# w20-cloudV1-_3_3_OHW.net
KiCad netlist of a schematic drawn in EAGLE
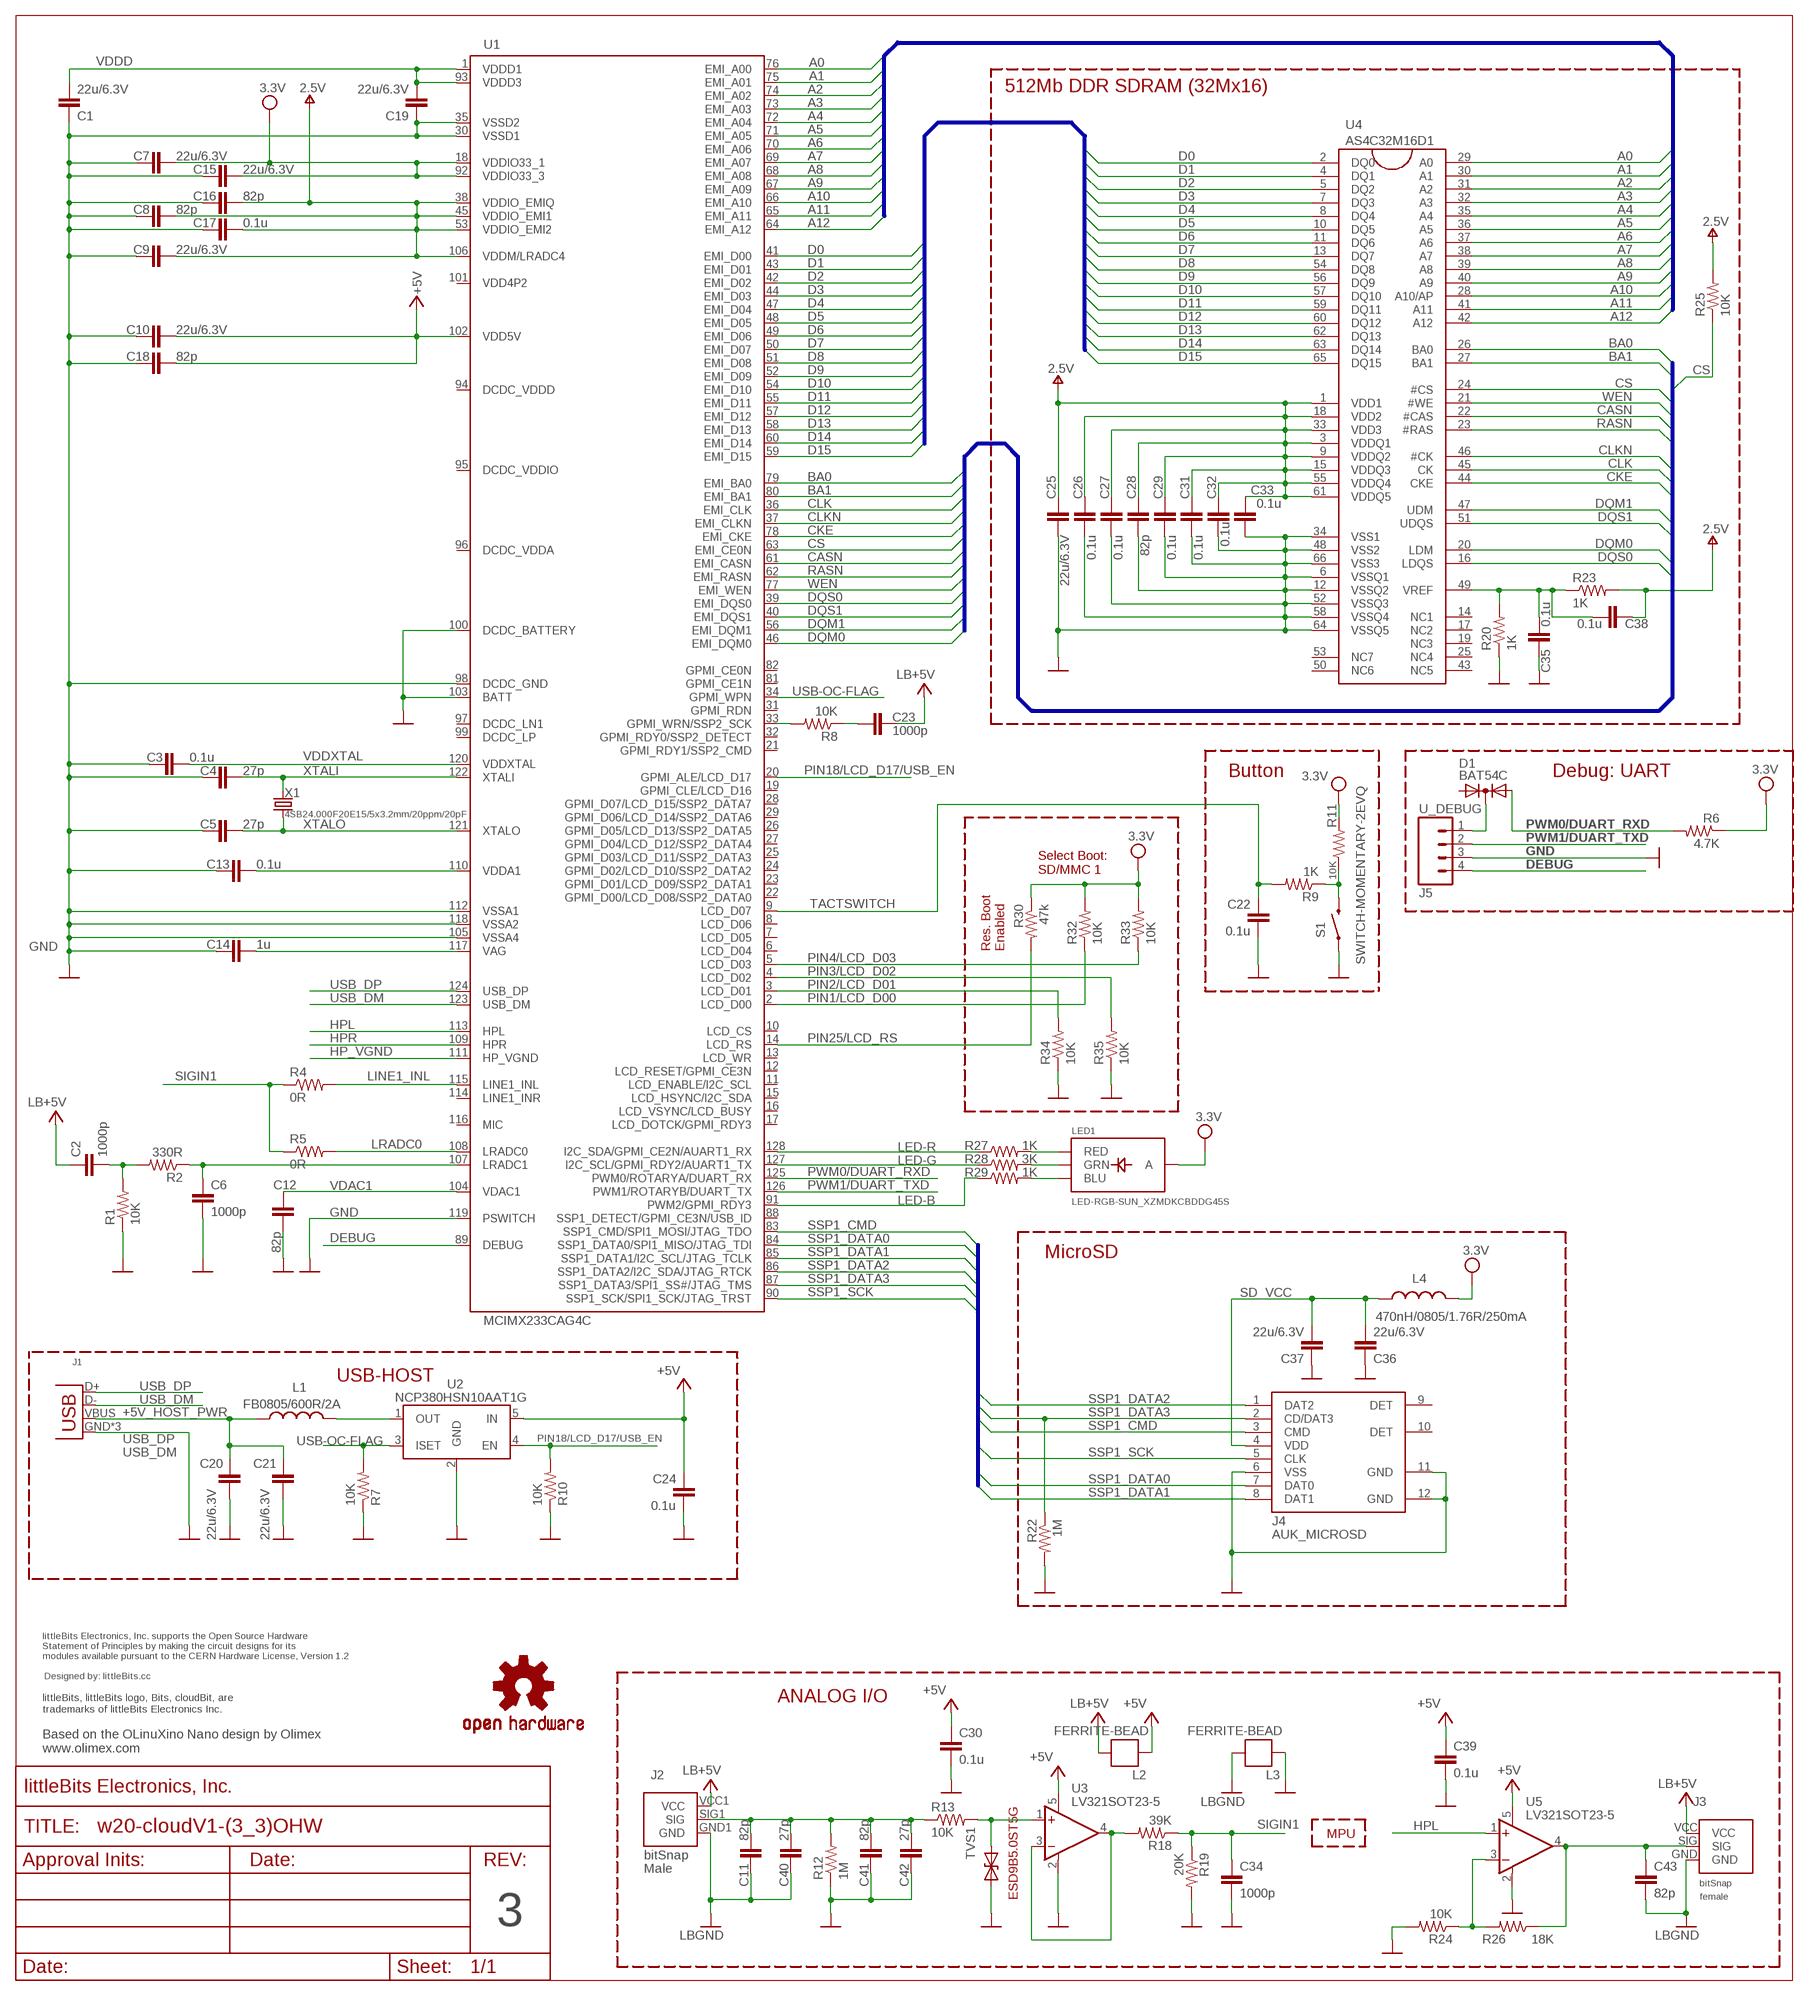
[diagram p0: schematic, sheet 1]

(export (version "E")
  (design (tool "Eeschema 10.0.6"))
  (components
    (comp (ref "C1")
      (value "22u/6.3V")
      (footprint "eagle-import:CAP-0603")
      (libsource (lib "eagle-import") (part "CAPCAP-0603"))
    )
    (comp (ref "C2")
      (value "1000p")
      (footprint "eagle-import:CAP-0603")
      (libsource (lib "eagle-import") (part "CAPCAP-0603"))
    )
    (comp (ref "C3")
      (value "0.1u")
      (footprint "eagle-import:CAP-0402")
      (libsource (lib "eagle-import") (part "CAPCAP-0402"))
    )
    (comp (ref "C4")
      (value "27p")
      (footprint "eagle-import:CAP-0402")
      (libsource (lib "eagle-import") (part "CAPCAP-0402"))
    )
    (comp (ref "C5")
      (value "27p")
      (footprint "eagle-import:CAP-0402")
      (libsource (lib "eagle-import") (part "CAPCAP-0402"))
    )
    (comp (ref "C6")
      (value "1000p")
      (footprint "eagle-import:CAP-0402")
      (libsource (lib "eagle-import") (part "CAPCAP-0402"))
    )
    (comp (ref "C7")
      (value "22u/6.3V")
      (footprint "eagle-import:CAP-0603")
      (libsource (lib "eagle-import") (part "CAPCAP-0603"))
    )
    (comp (ref "C8")
      (value "82p")
      (footprint "eagle-import:CAP-0402")
      (libsource (lib "eagle-import") (part "CAPCAP-0402"))
    )
    (comp (ref "C9")
      (value "22u/6.3V")
      (footprint "eagle-import:CAP-0603")
      (libsource (lib "eagle-import") (part "CAPCAP-0603"))
    )
    (comp (ref "C10")
      (value "22u/6.3V")
      (footprint "eagle-import:CAP-0603")
      (libsource (lib "eagle-import") (part "CAPCAP-0603"))
    )
    (comp (ref "C11")
      (value "82p")
      (footprint "eagle-import:CAP-0402")
      (libsource (lib "eagle-import") (part "CAPCAP-0402"))
    )
    (comp (ref "C12")
      (value "82p")
      (footprint "eagle-import:CAP-0402")
      (libsource (lib "eagle-import") (part "CAPCAP-0402"))
    )
    (comp (ref "C13")
      (value "0.1u")
      (footprint "eagle-import:CAP-0402")
      (libsource (lib "eagle-import") (part "CAPCAP-0402"))
    )
    (comp (ref "C14")
      (value "1u")
      (footprint "eagle-import:CAP-0402")
      (libsource (lib "eagle-import") (part "CAPCAP-0402"))
    )
    (comp (ref "C15")
      (value "22u/6.3V")
      (footprint "eagle-import:CAP-0603")
      (libsource (lib "eagle-import") (part "CAPCAP-0603"))
    )
    (comp (ref "C16")
      (value "82p")
      (footprint "eagle-import:CAP-0402")
      (libsource (lib "eagle-import") (part "CAPCAP-0402"))
    )
    (comp (ref "C17")
      (value "0.1u")
      (footprint "eagle-import:CAP-0402")
      (libsource (lib "eagle-import") (part "CAPCAP-0402"))
    )
    (comp (ref "C18")
      (value "82p")
      (footprint "eagle-import:CAP-0402")
      (libsource (lib "eagle-import") (part "CAPCAP-0402"))
    )
    (comp (ref "C19")
      (value "22u/6.3V")
      (footprint "eagle-import:CAP-0603")
      (libsource (lib "eagle-import") (part "CAPCAP-0603"))
    )
    (comp (ref "C20")
      (value "22u/6.3V")
      (footprint "eagle-import:CAP-0603")
      (libsource (lib "eagle-import") (part "CAPCAP-0603"))
    )
    (comp (ref "C21")
      (value "22u/6.3V")
      (footprint "eagle-import:CAP-0603")
      (libsource (lib "eagle-import") (part "CAPCAP-0603"))
    )
    (comp (ref "C22")
      (value "0.1u")
      (footprint "eagle-import:CAP-0402")
      (libsource (lib "eagle-import") (part "CAPCAP-0402"))
    )
    (comp (ref "C23")
      (value "1000p")
      (footprint "eagle-import:CAP-0603")
      (libsource (lib "eagle-import") (part "CAPCAP-0603"))
    )
    (comp (ref "C24")
      (value "0.1u")
      (footprint "eagle-import:CAP-0402")
      (libsource (lib "eagle-import") (part "CAPCAP-0402"))
    )
    (comp (ref "C25")
      (value "22u/6.3V")
      (footprint "eagle-import:CAP-0603")
      (libsource (lib "eagle-import") (part "CAPCAP-0603"))
    )
    (comp (ref "C26")
      (value "0.1u")
      (footprint "eagle-import:CAP-0402")
      (libsource (lib "eagle-import") (part "CAPCAP-0402"))
    )
    (comp (ref "C27")
      (value "0.1u")
      (footprint "eagle-import:CAP-0402")
      (libsource (lib "eagle-import") (part "CAPCAP-0402"))
    )
    (comp (ref "C28")
      (value "82p")
      (footprint "eagle-import:CAP-0402")
      (libsource (lib "eagle-import") (part "CAPCAP-0402"))
    )
    (comp (ref "C29")
      (value "0.1u")
      (footprint "eagle-import:CAP-0402")
      (libsource (lib "eagle-import") (part "CAPCAP-0402"))
    )
    (comp (ref "C30")
      (value "0.1u")
      (footprint "eagle-import:CAP-0402")
      (libsource (lib "eagle-import") (part "CAPCAP-0402"))
    )
    (comp (ref "C31")
      (value "0.1u")
      (footprint "eagle-import:CAP-0402")
      (libsource (lib "eagle-import") (part "CAPCAP-0402"))
    )
    (comp (ref "C32")
      (value "0.1u")
      (footprint "eagle-import:CAP-0402")
      (libsource (lib "eagle-import") (part "CAPCAP-0402"))
    )
    (comp (ref "C33")
      (value "0.1u")
      (footprint "eagle-import:CAP-0402")
      (libsource (lib "eagle-import") (part "CAPCAP-0402"))
    )
    (comp (ref "C34")
      (value "1000p")
      (footprint "eagle-import:CAP-0402")
      (libsource (lib "eagle-import") (part "CAPCAP-0402"))
    )
    (comp (ref "C35")
      (value "0.1u")
      (footprint "eagle-import:CAP-0402")
      (libsource (lib "eagle-import") (part "CAPCAP-0402"))
    )
    (comp (ref "C36")
      (value "22u/6.3V")
      (footprint "eagle-import:CAP-0603")
      (libsource (lib "eagle-import") (part "CAPCAP-0603"))
    )
    (comp (ref "C37")
      (value "22u/6.3V")
      (footprint "eagle-import:CAP-0603")
      (libsource (lib "eagle-import") (part "CAPCAP-0603"))
    )
    (comp (ref "C38")
      (value "0.1u")
      (footprint "eagle-import:CAP-0402")
      (libsource (lib "eagle-import") (part "CAPCAP-0402"))
    )
    (comp (ref "C39")
      (value "0.1u")
      (footprint "eagle-import:CAP-0402")
      (libsource (lib "eagle-import") (part "CAPCAP-0402"))
    )
    (comp (ref "C40")
      (value "27p")
      (footprint "eagle-import:CAP-0402")
      (libsource (lib "eagle-import") (part "CAPCAP-0402"))
    )
    (comp (ref "C41")
      (value "82p")
      (footprint "eagle-import:CAP-0402")
      (libsource (lib "eagle-import") (part "CAPCAP-0402"))
    )
    (comp (ref "C42")
      (value "27p")
      (footprint "eagle-import:CAP-0402")
      (libsource (lib "eagle-import") (part "CAPCAP-0402"))
    )
    (comp (ref "C43")
      (value "82p")
      (footprint "eagle-import:CAP-0402")
      (libsource (lib "eagle-import") (part "CAPCAP-0402"))
    )
    (comp (ref "D1")
      (value "BAT54C")
      (footprint "eagle-import:SOT23C")
      (libsource (lib "eagle-import") (part "DIODE_AC-CA_"))
    )
    (comp (ref "J1")
      (value "USBFEMALE")
      (footprint "eagle-import:USB-A-H-FEMALE")
      (libsource (lib "eagle-import") (part "USBFEMALE"))
    )
    (comp (ref "J2")
      (value "BITSNAP_V03_MALE")
      (footprint "eagle-import:BITSNAP_V03_MALE")
      (libsource (lib "eagle-import") (part "BITSNAP_V03_MALE"))
    )
    (comp (ref "J3")
      (value "BITSNAP_V03_FEMALE")
      (footprint "eagle-import:BITSNAP_V03_FEMALE")
      (libsource (lib "eagle-import") (part "BITSNAP_V03_FEMALE"))
    )
    (comp (ref "J4")
      (value "AUK_MICROSD")
      (footprint "eagle-import:AUK_TFC08WP01-R1K-H")
      (libsource (lib "eagle-import") (part "AUK_MICROSD"))
    )
    (comp (ref "J5")
      (value "U_DEBUG")
      (footprint "eagle-import:SIP4-SM-0.1IN-NOS.S.")
      (libsource (lib "eagle-import") (part "HDR-4SM_SML"))
    )
    (comp (ref "L1")
      (value "FB0805/600R/2A")
      (footprint "eagle-import:L0805_5MIL_DWS")
      (libsource (lib "eagle-import") (part "L-USL0805_5MIL_DWS"))
    )
    (comp (ref "L2")
      (value "FERRITE-BEAD")
      (footprint "eagle-import:R0603")
      (libsource (lib "eagle-import") (part "FERRITE-BEAD"))
    )
    (comp (ref "L3")
      (value "FERRITE-BEAD")
      (footprint "eagle-import:R0603")
      (libsource (lib "eagle-import") (part "FERRITE-BEAD"))
    )
    (comp (ref "L4")
      (value "470nH/0805/1.76R/250mA")
      (footprint "eagle-import:L0805_5MIL_DWS")
      (libsource (lib "eagle-import") (part "L-USL0805_5MIL_DWS"))
    )
    (comp (ref "LED1")
      (value "LED-RGB-SUN_XZMDKCBDDG45S")
      (footprint "eagle-import:LED-RGB-SUN_XZMDKCBDDG45S")
      (libsource (lib "eagle-import") (part "LED-RGB-SUN_XZMDKCBDDG45S"))
    )
    (comp (ref "R1")
      (value "10K")
      (footprint "eagle-import:RES-0603")
      (libsource (lib "eagle-import") (part "RESISTOR0603"))
    )
    (comp (ref "R2")
      (value "330R")
      (footprint "eagle-import:RES-0603")
      (libsource (lib "eagle-import") (part "RESISTOR0603"))
    )
    (comp (ref "R4")
      (value "0R")
      (footprint "eagle-import:RES-0603")
      (libsource (lib "eagle-import") (part "RESISTOR0603"))
    )
    (comp (ref "R5")
      (value "0R")
      (footprint "eagle-import:RES-0603")
      (libsource (lib "eagle-import") (part "RESISTOR0603"))
    )
    (comp (ref "R6")
      (value "4.7K")
      (footprint "eagle-import:RES-0603")
      (libsource (lib "eagle-import") (part "RESISTOR0603"))
    )
    (comp (ref "R7")
      (value "10K")
      (footprint "eagle-import:RES-0603")
      (libsource (lib "eagle-import") (part "RESISTOR0603"))
    )
    (comp (ref "R8")
      (value "10K")
      (footprint "eagle-import:RES-0603")
      (libsource (lib "eagle-import") (part "RESISTOR0603"))
    )
    (comp (ref "R9")
      (value "1K")
      (footprint "eagle-import:RES-0603")
      (libsource (lib "eagle-import") (part "RESISTOR0603"))
    )
    (comp (ref "R10")
      (value "10K")
      (footprint "eagle-import:RES-0603")
      (libsource (lib "eagle-import") (part "RESISTOR0603"))
    )
    (comp (ref "R11")
      (value "10K")
      (footprint "eagle-import:RES-0603")
      (libsource (lib "eagle-import") (part "RESISTOR0603"))
    )
    (comp (ref "R12")
      (value "1M")
      (footprint "eagle-import:RES-0603")
      (libsource (lib "eagle-import") (part "RESISTOR0603"))
    )
    (comp (ref "R13")
      (value "10K")
      (footprint "eagle-import:RES-0603")
      (libsource (lib "eagle-import") (part "RESISTOR0603"))
    )
    (comp (ref "R18")
      (value "39K")
      (footprint "eagle-import:RES-0603")
      (libsource (lib "eagle-import") (part "RESISTOR0603"))
    )
    (comp (ref "R19")
      (value "20K")
      (footprint "eagle-import:RES-0603")
      (libsource (lib "eagle-import") (part "RESISTOR0603"))
    )
    (comp (ref "R20")
      (value "1K")
      (footprint "eagle-import:RES-0603")
      (libsource (lib "eagle-import") (part "RESISTOR0603"))
    )
    (comp (ref "R22")
      (value "1M")
      (footprint "eagle-import:RES-0603")
      (libsource (lib "eagle-import") (part "RESISTOR0603"))
    )
    (comp (ref "R23")
      (value "1K")
      (footprint "eagle-import:RES-0603")
      (libsource (lib "eagle-import") (part "RESISTOR0603"))
    )
    (comp (ref "R24")
      (value "10K")
      (footprint "eagle-import:RES-0603")
      (libsource (lib "eagle-import") (part "RESISTOR0603"))
    )
    (comp (ref "R25")
      (value "10K")
      (footprint "eagle-import:RES-0603")
      (libsource (lib "eagle-import") (part "RESISTOR0603"))
    )
    (comp (ref "R26")
      (value "18K")
      (footprint "eagle-import:RES-0603")
      (libsource (lib "eagle-import") (part "RESISTOR0603"))
    )
    (comp (ref "R27")
      (value "1K")
      (footprint "eagle-import:RES-0603")
      (libsource (lib "eagle-import") (part "RESISTOR0603"))
    )
    (comp (ref "R28")
      (value "3K")
      (footprint "eagle-import:RES-0603")
      (libsource (lib "eagle-import") (part "RESISTOR0603"))
    )
    (comp (ref "R29")
      (value "1K")
      (footprint "eagle-import:RES-0603")
      (libsource (lib "eagle-import") (part "RESISTOR0603"))
    )
    (comp (ref "R30")
      (value "47k")
      (footprint "eagle-import:RES-0603")
      (libsource (lib "eagle-import") (part "RESISTOR0603"))
    )
    (comp (ref "R32")
      (value "10K")
      (footprint "eagle-import:RES-0603")
      (libsource (lib "eagle-import") (part "RESISTOR0603"))
    )
    (comp (ref "R33")
      (value "10K")
      (footprint "eagle-import:RES-0603")
      (libsource (lib "eagle-import") (part "RESISTOR0603"))
    )
    (comp (ref "R34")
      (value "10K")
      (footprint "eagle-import:RES-0603")
      (libsource (lib "eagle-import") (part "RESISTOR0603"))
    )
    (comp (ref "R35")
      (value "10K")
      (footprint "eagle-import:RES-0603")
      (libsource (lib "eagle-import") (part "RESISTOR0603"))
    )
    (comp (ref "S1")
      (value "SWITCH-MOMENTARY-2EVQ")
      (footprint "eagle-import:TACTILE-SWITCH-EVQ-PE104K")
      (libsource (lib "eagle-import") (part "SWITCH-MOMENTARY-2EVQ"))
    )
    (comp (ref "TVS1")
      (value "DIODE-TVSSOD-923")
      (footprint "eagle-import:SOD-923")
      (fields (field (name "MPN") "ESD9B5.0ST5G"))
      (libsource (lib "eagle-import") (part "DIODE-TVSSOD-923"))
    )
    (comp (ref "U$2")
      (value "OSHWCREDIT")
      (footprint "eagle-import:OSHWCREDIT")
      (libsource (lib "eagle-import") (part "OSHWCREDIT"))
    )
    (comp (ref "U$4")
      (value "OSHW-LOGOL")
      (footprint "eagle-import:OSHW-LOGO-L")
      (libsource (lib "eagle-import") (part "OSHW-LOGOL"))
    )
    (comp (ref "U$5")
      (value "FRAME-LETTER-OHWOHW")
      (footprint "eagle-import:FABDWG01-OHW")
      (libsource (lib "eagle-import") (part "FRAME-LETTER-OHWOHW"))
    )
    (comp (ref "U1")
      (value "MCIMX233CAG4C")
      (footprint "eagle-import:TQFP128LD")
      (libsource (lib "eagle-import") (part "MCIMX233DAG4B_LD"))
    )
    (comp (ref "U2")
      (value "NCP380HSN10AAT1G")
      (footprint "eagle-import:SOT23-5")
      (libsource (lib "eagle-import") (part "SY6280"))
    )
    (comp (ref "U3")
      (value "LV321SOT23-5")
      (footprint "eagle-import:SOT23-5")
      (libsource (lib "eagle-import") (part "LV321SOT23-5"))
    )
    (comp (ref "U4")
      (value "AS4C32M16D1")
      (footprint "eagle-import:66TSOP-II")
      (libsource (lib "eagle-import") (part "HY5DU121622D(L)T(P)-J"))
    )
    (comp (ref "U5")
      (value "LV321SOT23-5")
      (footprint "eagle-import:SOT23-5")
      (libsource (lib "eagle-import") (part "LV321SOT23-5"))
    )
    (comp (ref "X1")
      (value "4SB24.000F20E15/5x3.2mm/20ppm/20pF")
      (footprint "eagle-import:HCX-4S")
      (libsource (lib "eagle-import") (part "HC49/S_E4SB25.000F20E15"))
    )
  )
  (nets
    (net (code "1") (name "+5V") (class "Default")
      (node (ref "C10") (pin "2") (pinfunction "2_2") (pintype "passive"))
      (node (ref "C18") (pin "2") (pinfunction "2_2") (pintype "passive"))
      (node (ref "C24") (pin "1") (pinfunction "1_1") (pintype "passive"))
      (node (ref "C30") (pin "1") (pinfunction "1_1") (pintype "passive"))
      (node (ref "C39") (pin "1") (pinfunction "1_1") (pintype "passive"))
      (node (ref "L2") (pin "2") (pinfunction "P$2_2") (pintype "bidirectional"))
      (node (ref "U1") (pin "102") (pinfunction "VDD5V_102") (pintype "power_in"))
      (node (ref "U2") (pin "5") (pinfunction "IN_5") (pintype "power_in"))
      (node (ref "U3") (pin "5") (pinfunction "V+_5") (pintype "power_in"))
      (node (ref "U5") (pin "5") (pinfunction "V+_5") (pintype "power_in"))
    )
    (net (code "2") (name "/+5V_HOST_PWR") (class "Default")
      (node (ref "C20") (pin "1") (pinfunction "1_1") (pintype "passive"))
      (node (ref "C21") (pin "1") (pinfunction "1_1") (pintype "passive"))
      (node (ref "J1") (pin "VBUS") (pinfunction "VBUS_VBUS") (pintype "bidirectional"))
      (node (ref "L1") (pin "1") (pinfunction "1_1") (pintype "passive"))
    )
    (net (code "3") (name "/A0") (class "Default")
      (node (ref "U1") (pin "76") (pinfunction "EMI_A00_76") (pintype "bidirectional"))
      (node (ref "U4") (pin "29") (pinfunction "A0_29") (pintype "input"))
    )
    (net (code "4") (name "/A1") (class "Default")
      (node (ref "U1") (pin "75") (pinfunction "EMI_A01_75") (pintype "bidirectional"))
      (node (ref "U4") (pin "30") (pinfunction "A1_30") (pintype "input"))
    )
    (net (code "5") (name "/A2") (class "Default")
      (node (ref "U1") (pin "74") (pinfunction "EMI_A02_74") (pintype "bidirectional"))
      (node (ref "U4") (pin "31") (pinfunction "A2_31") (pintype "input"))
    )
    (net (code "6") (name "/A3") (class "Default")
      (node (ref "U1") (pin "73") (pinfunction "EMI_A03_73") (pintype "bidirectional"))
      (node (ref "U4") (pin "32") (pinfunction "A3_32") (pintype "input"))
    )
    (net (code "7") (name "/A4") (class "Default")
      (node (ref "U1") (pin "72") (pinfunction "EMI_A04_72") (pintype "bidirectional"))
      (node (ref "U4") (pin "35") (pinfunction "A4_35") (pintype "input"))
    )
    (net (code "8") (name "/A5") (class "Default")
      (node (ref "U1") (pin "71") (pinfunction "EMI_A05_71") (pintype "bidirectional"))
      (node (ref "U4") (pin "36") (pinfunction "A5_36") (pintype "input"))
    )
    (net (code "9") (name "/A6") (class "Default")
      (node (ref "U1") (pin "70") (pinfunction "EMI_A06_70") (pintype "bidirectional"))
      (node (ref "U4") (pin "37") (pinfunction "A6_37") (pintype "input"))
    )
    (net (code "10") (name "/A7") (class "Default")
      (node (ref "U1") (pin "69") (pinfunction "EMI_A07_69") (pintype "bidirectional"))
      (node (ref "U4") (pin "38") (pinfunction "A7_38") (pintype "input"))
    )
    (net (code "11") (name "/A8") (class "Default")
      (node (ref "U1") (pin "68") (pinfunction "EMI_A08_68") (pintype "bidirectional"))
      (node (ref "U4") (pin "39") (pinfunction "A8_39") (pintype "input"))
    )
    (net (code "12") (name "/A9") (class "Default")
      (node (ref "U1") (pin "67") (pinfunction "EMI_A09_67") (pintype "bidirectional"))
      (node (ref "U4") (pin "40") (pinfunction "A9_40") (pintype "input"))
    )
    (net (code "13") (name "/A10") (class "Default")
      (node (ref "U1") (pin "66") (pinfunction "EMI_A10_66") (pintype "bidirectional"))
      (node (ref "U4") (pin "28") (pinfunction "A10/AP_28") (pintype "input"))
    )
    (net (code "14") (name "/A11") (class "Default")
      (node (ref "U1") (pin "65") (pinfunction "EMI_A11_65") (pintype "bidirectional"))
      (node (ref "U4") (pin "41") (pinfunction "A11_41") (pintype "input"))
    )
    (net (code "15") (name "/A12") (class "Default")
      (node (ref "U1") (pin "64") (pinfunction "EMI_A12_64") (pintype "bidirectional"))
      (node (ref "U4") (pin "42") (pinfunction "A12_42") (pintype "input"))
    )
    (net (code "16") (name "/BA0") (class "Default")
      (node (ref "U1") (pin "79") (pinfunction "EMI_BA0_79") (pintype "output"))
      (node (ref "U4") (pin "26") (pinfunction "BA0_26") (pintype "input"))
    )
    (net (code "17") (name "/BA1") (class "Default")
      (node (ref "U1") (pin "80") (pinfunction "EMI_BA1_80") (pintype "output"))
      (node (ref "U4") (pin "27") (pinfunction "BA1_27") (pintype "input"))
    )
    (net (code "18") (name "/CASN") (class "Default")
      (node (ref "U1") (pin "61") (pinfunction "EMI_CASN_61") (pintype "output"))
      (node (ref "U4") (pin "22") (pinfunction "#CAS_22") (pintype "input"))
    )
    (net (code "19") (name "/CKE") (class "Default")
      (node (ref "U1") (pin "78") (pinfunction "EMI_CKE_78") (pintype "output"))
      (node (ref "U4") (pin "44") (pinfunction "CKE_44") (pintype "input"))
    )
    (net (code "20") (name "/CLK") (class "Default")
      (node (ref "U1") (pin "36") (pinfunction "EMI_CLK_36") (pintype "output"))
      (node (ref "U4") (pin "45") (pinfunction "CK_45") (pintype "input"))
    )
    (net (code "21") (name "/CLKN") (class "Default")
      (node (ref "U1") (pin "37") (pinfunction "EMI_CLKN_37") (pintype "output"))
      (node (ref "U4") (pin "46") (pinfunction "#CK_46") (pintype "input"))
    )
    (net (code "22") (name "/CS") (class "Default")
      (node (ref "R25") (pin "1") (pinfunction "1_1") (pintype "passive"))
      (node (ref "U1") (pin "63") (pinfunction "EMI_CE0N_63") (pintype "output"))
      (node (ref "U4") (pin "24") (pinfunction "#CS_24") (pintype "input"))
    )
    (net (code "23") (name "/D0") (class "Default")
      (node (ref "U1") (pin "41") (pinfunction "EMI_D00_41") (pintype "bidirectional"))
      (node (ref "U4") (pin "2") (pinfunction "DQ0_2") (pintype "bidirectional"))
    )
    (net (code "24") (name "/D1") (class "Default")
      (node (ref "U1") (pin "43") (pinfunction "EMI_D01_43") (pintype "bidirectional"))
      (node (ref "U4") (pin "4") (pinfunction "DQ1_4") (pintype "bidirectional"))
    )
    (net (code "25") (name "/D2") (class "Default")
      (node (ref "U1") (pin "42") (pinfunction "EMI_D02_42") (pintype "bidirectional"))
      (node (ref "U4") (pin "5") (pinfunction "DQ2_5") (pintype "bidirectional"))
    )
    (net (code "26") (name "/D3") (class "Default")
      (node (ref "U1") (pin "44") (pinfunction "EMI_D03_44") (pintype "bidirectional"))
      (node (ref "U4") (pin "7") (pinfunction "DQ3_7") (pintype "bidirectional"))
    )
    (net (code "27") (name "/D4") (class "Default")
      (node (ref "U1") (pin "47") (pinfunction "EMI_D04_47") (pintype "bidirectional"))
      (node (ref "U4") (pin "8") (pinfunction "DQ4_8") (pintype "bidirectional"))
    )
    (net (code "28") (name "/D5") (class "Default")
      (node (ref "U1") (pin "48") (pinfunction "EMI_D05_48") (pintype "bidirectional"))
      (node (ref "U4") (pin "10") (pinfunction "DQ5_10") (pintype "bidirectional"))
    )
    (net (code "29") (name "/D6") (class "Default")
      (node (ref "U1") (pin "49") (pinfunction "EMI_D06_49") (pintype "bidirectional"))
      (node (ref "U4") (pin "11") (pinfunction "DQ6_11") (pintype "bidirectional"))
    )
    (net (code "30") (name "/D7") (class "Default")
      (node (ref "U1") (pin "50") (pinfunction "EMI_D07_50") (pintype "bidirectional"))
      (node (ref "U4") (pin "13") (pinfunction "DQ7_13") (pintype "bidirectional"))
    )
    (net (code "31") (name "/D8") (class "Default")
      (node (ref "U1") (pin "51") (pinfunction "EMI_D08_51") (pintype "bidirectional"))
      (node (ref "U4") (pin "54") (pinfunction "DQ8_54") (pintype "bidirectional"))
    )
    (net (code "32") (name "/D9") (class "Default")
      (node (ref "U1") (pin "52") (pinfunction "EMI_D09_52") (pintype "bidirectional"))
      (node (ref "U4") (pin "56") (pinfunction "DQ9_56") (pintype "bidirectional"))
    )
    (net (code "33") (name "/D10") (class "Default")
      (node (ref "U1") (pin "54") (pinfunction "EMI_D10_54") (pintype "bidirectional"))
      (node (ref "U4") (pin "57") (pinfunction "DQ10_57") (pintype "bidirectional"))
    )
    (net (code "34") (name "/D11") (class "Default")
      (node (ref "U1") (pin "55") (pinfunction "EMI_D11_55") (pintype "bidirectional"))
      (node (ref "U4") (pin "59") (pinfunction "DQ11_59") (pintype "bidirectional"))
    )
    (net (code "35") (name "/D12") (class "Default")
      (node (ref "U1") (pin "57") (pinfunction "EMI_D12_57") (pintype "bidirectional"))
      (node (ref "U4") (pin "60") (pinfunction "DQ12_60") (pintype "bidirectional"))
    )
    (net (code "36") (name "/D13") (class "Default")
      (node (ref "U1") (pin "58") (pinfunction "EMI_D13_58") (pintype "bidirectional"))
      (node (ref "U4") (pin "62") (pinfunction "DQ13_62") (pintype "bidirectional"))
    )
    (net (code "37") (name "/D14") (class "Default")
      (node (ref "U1") (pin "60") (pinfunction "EMI_D14_60") (pintype "bidirectional"))
      (node (ref "U4") (pin "63") (pinfunction "DQ14_63") (pintype "bidirectional"))
    )
    (net (code "38") (name "/D15") (class "Default")
      (node (ref "U1") (pin "59") (pinfunction "EMI_D15_59") (pintype "bidirectional"))
      (node (ref "U4") (pin "65") (pinfunction "DQ15_65") (pintype "bidirectional"))
    )
    (net (code "39") (name "/DCDC_VDDA") (class "Default")
      (node (ref "U1") (pin "96") (pinfunction "DCDC_VDDA_96") (pintype "power_in"))
    )
    (net (code "40") (name "/DCDC_VDDD") (class "Default")
      (node (ref "U1") (pin "94") (pinfunction "DCDC_VDDD_94") (pintype "power_in"))
    )
    (net (code "41") (name "/DCDC_VDDIO") (class "Default")
      (node (ref "U1") (pin "95") (pinfunction "DCDC_VDDIO_95") (pintype "power_in"))
    )
    (net (code "42") (name "/DEBUG") (class "Default")
      (node (ref "J5") (pin "4") (pinfunction "4_4") (pintype "passive"))
      (node (ref "U1") (pin "89") (pinfunction "DEBUG_89") (pintype "bidirectional"))
    )
    (net (code "43") (name "/DQM0") (class "Default")
      (node (ref "U1") (pin "46") (pinfunction "EMI_DQM0_46") (pintype "output"))
      (node (ref "U4") (pin "20") (pinfunction "LDM_20") (pintype "input"))
    )
    (net (code "44") (name "/DQM1") (class "Default")
      (node (ref "U1") (pin "56") (pinfunction "EMI_DQM1_56") (pintype "output"))
      (node (ref "U4") (pin "47") (pinfunction "UDM_47") (pintype "input"))
    )
    (net (code "45") (name "/DQS0") (class "Default")
      (node (ref "U1") (pin "39") (pinfunction "EMI_DQS0_39") (pintype "output"))
      (node (ref "U4") (pin "16") (pinfunction "LDQS_16") (pintype "bidirectional"))
    )
    (net (code "46") (name "/DQS1") (class "Default")
      (node (ref "U1") (pin "40") (pinfunction "EMI_DQS1_40") (pintype "output"))
      (node (ref "U4") (pin "51") (pinfunction "UDQS_51") (pintype "input"))
    )
    (net (code "47") (name "/HPL") (class "Default")
      (node (ref "U1") (pin "113") (pinfunction "HPL_113") (pintype "output"))
      (node (ref "U5") (pin "1") (pinfunction "+IN_1") (pintype "input"))
    )
    (net (code "48") (name "/HPR") (class "Default")
      (node (ref "U1") (pin "109") (pinfunction "HPR_109") (pintype "output"))
    )
    (net (code "49") (name "/HP_VGND") (class "Default")
      (node (ref "U1") (pin "111") (pinfunction "HP_VGND_111") (pintype "power_in"))
    )
    (net (code "50") (name "/LED-B") (class "Default")
      (node (ref "R29") (pin "1") (pinfunction "1_1") (pintype "passive"))
      (node (ref "U1") (pin "91") (pinfunction "PWM2/GPMI_RDY3_91") (pintype "bidirectional"))
    )
    (net (code "51") (name "/LED-G") (class "Default")
      (node (ref "R28") (pin "1") (pinfunction "1_1") (pintype "passive"))
      (node (ref "U1") (pin "127") (pinfunction "I2C_SCL/GPMI_RDY2/AUART1_TX_127") (pintype "bidirectional"))
    )
    (net (code "52") (name "/LED-R") (class "Default")
      (node (ref "R27") (pin "1") (pinfunction "1_1") (pintype "passive"))
      (node (ref "U1") (pin "128") (pinfunction "I2C_SDA/GPMI_CE2N/AUART1_RX_128") (pintype "bidirectional"))
    )
    (net (code "53") (name "/LINE1_INL") (class "Default")
      (node (ref "R4") (pin "2") (pinfunction "2_2") (pintype "passive"))
      (node (ref "U1") (pin "115") (pinfunction "LINE1_INL_115") (pintype "input"))
    )
    (net (code "54") (name "/LRADC0") (class "Default")
      (node (ref "R5") (pin "2") (pinfunction "2_2") (pintype "passive"))
      (node (ref "U1") (pin "108") (pinfunction "LRADC0_108") (pintype "bidirectional"))
    )
    (net (code "55") (name "/PIN1{slash}LCD_D00") (class "Default")
      (node (ref "R32") (pin "1") (pinfunction "1_1") (pintype "passive"))
      (node (ref "U1") (pin "2") (pinfunction "LCD_D00_2") (pintype "bidirectional"))
    )
    (net (code "56") (name "/PIN2{slash}LCD_D01") (class "Default")
      (node (ref "R34") (pin "2") (pinfunction "2_2") (pintype "passive"))
      (node (ref "U1") (pin "3") (pinfunction "LCD_D01_3") (pintype "bidirectional"))
    )
    (net (code "57") (name "/PIN3{slash}LCD_D02") (class "Default")
      (node (ref "R35") (pin "2") (pinfunction "2_2") (pintype "passive"))
      (node (ref "U1") (pin "4") (pinfunction "LCD_D02_4") (pintype "bidirectional"))
    )
    (net (code "58") (name "/PIN4{slash}LCD_D03") (class "Default")
      (node (ref "R33") (pin "1") (pinfunction "1_1") (pintype "passive"))
      (node (ref "U1") (pin "5") (pinfunction "LCD_D03_5") (pintype "bidirectional"))
    )
    (net (code "59") (name "/PIN18{slash}LCD_D17{slash}USB_EN") (class "Default")
      (node (ref "R10") (pin "2") (pinfunction "2_2") (pintype "passive"))
      (node (ref "U1") (pin "20") (pinfunction "GPMI_ALE/LCD_D17_20") (pintype "bidirectional"))
      (node (ref "U2") (pin "4") (pinfunction "EN_4") (pintype "bidirectional"))
    )
    (net (code "60") (name "/PIN25{slash}LCD_RS") (class "Default")
      (node (ref "R30") (pin "2") (pinfunction "2_2") (pintype "passive"))
      (node (ref "U1") (pin "14") (pinfunction "LCD_RS_14") (pintype "bidirectional"))
    )
    (net (code "61") (name "/PWM0{slash}DUART_RXD") (class "Default")
      (node (ref "D1") (pin "2") (pinfunction "A2_2") (pintype "passive"))
      (node (ref "R6") (pin "2") (pinfunction "2_2") (pintype "passive"))
      (node (ref "U1") (pin "125") (pinfunction "PWM0/ROTARYA/DUART_RX_125") (pintype "bidirectional"))
    )
    (net (code "62") (name "/PWM1{slash}DUART_TXD") (class "Default")
      (node (ref "J5") (pin "2") (pinfunction "2_2") (pintype "passive"))
      (node (ref "U1") (pin "126") (pinfunction "PWM1/ROTARYB/DUART_TX_126") (pintype "bidirectional"))
    )
    (net (code "63") (name "/RASN") (class "Default")
      (node (ref "U1") (pin "62") (pinfunction "EMI_RASN_62") (pintype "output"))
      (node (ref "U4") (pin "23") (pinfunction "#RAS_23") (pintype "input"))
    )
    (net (code "64") (name "/SD_VCC") (class "Default")
      (node (ref "C36") (pin "2") (pinfunction "2_2") (pintype "passive"))
      (node (ref "C37") (pin "2") (pinfunction "2_2") (pintype "passive"))
      (node (ref "J4") (pin "4") (pinfunction "VDD_4") (pintype "bidirectional"))
      (node (ref "L4") (pin "2") (pinfunction "2_2") (pintype "passive"))
    )
    (net (code "65") (name "/SIGIN1") (class "Default")
      (node (ref "C34") (pin "1") (pinfunction "1_1") (pintype "passive"))
      (node (ref "R18") (pin "1") (pinfunction "1_1") (pintype "passive"))
      (node (ref "R19") (pin "1") (pinfunction "1_1") (pintype "passive"))
      (node (ref "R4") (pin "1") (pinfunction "1_1") (pintype "passive"))
      (node (ref "R5") (pin "1") (pinfunction "1_1") (pintype "passive"))
    )
    (net (code "66") (name "/SSP1_CMD") (class "Default")
      (node (ref "J4") (pin "3") (pinfunction "CMD_3") (pintype "bidirectional"))
      (node (ref "U1") (pin "83") (pinfunction "SSP1_CMD/SPI1_MOSI/JTAG_TDO_83") (pintype "bidirectional"))
    )
    (net (code "67") (name "/SSP1_DATA0") (class "Default")
      (node (ref "J4") (pin "7") (pinfunction "DAT0_7") (pintype "bidirectional"))
      (node (ref "U1") (pin "84") (pinfunction "SSP1_DATA0/SPI1_MISO/JTAG_TDI_84") (pintype "bidirectional"))
    )
    (net (code "68") (name "/SSP1_DATA1") (class "Default")
      (node (ref "J4") (pin "8") (pinfunction "DAT1_8") (pintype "bidirectional"))
      (node (ref "U1") (pin "85") (pinfunction "SSP1_DATA1/I2C_SCL/JTAG_TCLK_85") (pintype "bidirectional"))
    )
    (net (code "69") (name "/SSP1_DATA2") (class "Default")
      (node (ref "J4") (pin "1") (pinfunction "DAT2_1") (pintype "bidirectional"))
      (node (ref "U1") (pin "86") (pinfunction "SSP1_DATA2/I2C_SDA/JTAG_RTCK_86") (pintype "bidirectional"))
    )
    (net (code "70") (name "/SSP1_DATA3") (class "Default")
      (node (ref "J4") (pin "2") (pinfunction "CD/DAT3_2") (pintype "bidirectional"))
      (node (ref "R22") (pin "1") (pinfunction "1_1") (pintype "passive"))
      (node (ref "U1") (pin "87") (pinfunction "SSP1_DATA3/SPI1_SS#/JTAG_TMS_87") (pintype "bidirectional"))
    )
    (net (code "71") (name "/SSP1_SCK") (class "Default")
      (node (ref "J4") (pin "5") (pinfunction "CLK_5") (pintype "bidirectional"))
      (node (ref "U1") (pin "90") (pinfunction "SSP1_SCK/SPI1_SCK/JTAG_TRST_90") (pintype "bidirectional"))
    )
    (net (code "72") (name "/TACTSWITCH") (class "Default")
      (node (ref "C22") (pin "1") (pinfunction "1_1") (pintype "passive"))
      (node (ref "R9") (pin "2") (pinfunction "2_2") (pintype "passive"))
      (node (ref "U1") (pin "9") (pinfunction "LCD_D07_9") (pintype "bidirectional"))
    )
    (net (code "73") (name "/USB-OC-FLAG") (class "Default")
      (node (ref "R7") (pin "2") (pinfunction "2_2") (pintype "passive"))
      (node (ref "U1") (pin "34") (pinfunction "GPMI_WPN_34") (pintype "bidirectional"))
      (node (ref "U2") (pin "3") (pinfunction "ISET_3") (pintype "bidirectional"))
    )
    (net (code "74") (name "/USB_DM") (class "Default")
      (node (ref "J1") (pin "D-") (pinfunction "D-_D-") (pintype "bidirectional"))
      (node (ref "U1") (pin "123") (pinfunction "USB_DM_123") (pintype "bidirectional"))
    )
    (net (code "75") (name "/USB_DP") (class "Default")
      (node (ref "J1") (pin "D+") (pinfunction "D+_D+") (pintype "bidirectional"))
      (node (ref "U1") (pin "124") (pinfunction "USB_DP_124") (pintype "bidirectional"))
    )
    (net (code "76") (name "/VDAC1") (class "Default")
      (node (ref "C12") (pin "1") (pinfunction "1_1") (pintype "passive"))
      (node (ref "U1") (pin "104") (pinfunction "VDAC1_104") (pintype "output"))
    )
    (net (code "77") (name "/VDD4P2") (class "Default")
      (node (ref "U1") (pin "101") (pinfunction "VDD4P2_101") (pintype "power_in"))
    )
    (net (code "78") (name "/VDDD") (class "Default")
      (node (ref "C1") (pin "2") (pinfunction "2_2") (pintype "passive"))
      (node (ref "C19") (pin "2") (pinfunction "2_2") (pintype "passive"))
      (node (ref "U1") (pin "1") (pinfunction "VDDD1_1") (pintype "power_in"))
      (node (ref "U1") (pin "93") (pinfunction "VDDD3_93") (pintype "power_in"))
    )
    (net (code "79") (name "/VDDXTAL") (class "Default")
      (node (ref "C3") (pin "2") (pinfunction "2_2") (pintype "passive"))
      (node (ref "U1") (pin "120") (pinfunction "VDDXTAL_120") (pintype "passive"))
    )
    (net (code "80") (name "/WEN") (class "Default")
      (node (ref "U1") (pin "77") (pinfunction "EMI_WEN_77") (pintype "output"))
      (node (ref "U4") (pin "21") (pinfunction "#WE_21") (pintype "input"))
    )
    (net (code "81") (name "/XTALI") (class "Default")
      (node (ref "C4") (pin "2") (pinfunction "2_2") (pintype "passive"))
      (node (ref "U1") (pin "122") (pinfunction "XTALI_122") (pintype "input"))
      (node (ref "X1") (pin "2") (pinfunction "2_2") (pintype "passive"))
    )
    (net (code "82") (name "/XTALO") (class "Default")
      (node (ref "C5") (pin "2") (pinfunction "2_2") (pintype "passive"))
      (node (ref "U1") (pin "121") (pinfunction "XTALO_121") (pintype "output"))
      (node (ref "X1") (pin "1") (pinfunction "1_1") (pintype "passive"))
    )
    (net (code "83") (name "2.5V") (class "Default")
      (node (ref "C16") (pin "2") (pinfunction "2_2") (pintype "passive"))
      (node (ref "C17") (pin "2") (pinfunction "2_2") (pintype "passive"))
      (node (ref "C25") (pin "2") (pinfunction "2_2") (pintype "passive"))
      (node (ref "C26") (pin "2") (pinfunction "2_2") (pintype "passive"))
      (node (ref "C27") (pin "2") (pinfunction "2_2") (pintype "passive"))
      (node (ref "C28") (pin "2") (pinfunction "2_2") (pintype "passive"))
      (node (ref "C29") (pin "2") (pinfunction "2_2") (pintype "passive"))
      (node (ref "C31") (pin "2") (pinfunction "2_2") (pintype "passive"))
      (node (ref "C32") (pin "2") (pinfunction "2_2") (pintype "passive"))
      (node (ref "C33") (pin "2") (pinfunction "2_2") (pintype "passive"))
      (node (ref "C38") (pin "1") (pinfunction "1_1") (pintype "passive"))
      (node (ref "C8") (pin "2") (pinfunction "2_2") (pintype "passive"))
      (node (ref "C9") (pin "2") (pinfunction "2_2") (pintype "passive"))
      (node (ref "R23") (pin "2") (pinfunction "2_2") (pintype "passive"))
      (node (ref "R25") (pin "2") (pinfunction "2_2") (pintype "passive"))
      (node (ref "U1") (pin "106") (pinfunction "VDDM/LRADC4_106") (pintype "power_in"))
      (node (ref "U1") (pin "38") (pinfunction "VDDIO_EMIQ_38") (pintype "power_in"))
      (node (ref "U1") (pin "45") (pinfunction "VDDIO_EMI1_45") (pintype "power_in"))
      (node (ref "U1") (pin "53") (pinfunction "VDDIO_EMI2_53") (pintype "power_in"))
      (node (ref "U4") (pin "1") (pinfunction "VDD1_1") (pintype "power_in"))
      (node (ref "U4") (pin "15") (pinfunction "VDDQ3_15") (pintype "power_in"))
      (node (ref "U4") (pin "18") (pinfunction "VDD2_18") (pintype "power_in"))
      (node (ref "U4") (pin "3") (pinfunction "VDDQ1_3") (pintype "power_in"))
      (node (ref "U4") (pin "33") (pinfunction "VDD3_33") (pintype "power_in"))
      (node (ref "U4") (pin "55") (pinfunction "VDDQ4_55") (pintype "power_in"))
      (node (ref "U4") (pin "61") (pinfunction "VDDQ5_61") (pintype "power_in"))
      (node (ref "U4") (pin "9") (pinfunction "VDDQ2_9") (pintype "power_in"))
    )
    (net (code "84") (name "3.3V") (class "Default")
      (node (ref "C15") (pin "2") (pinfunction "2_2") (pintype "passive"))
      (node (ref "C7") (pin "2") (pinfunction "2_2") (pintype "passive"))
      (node (ref "L4") (pin "1") (pinfunction "1_1") (pintype "passive"))
      (node (ref "LED1") (pin "2") (pinfunction "A_2") (pintype "bidirectional"))
      (node (ref "R11") (pin "2") (pinfunction "2_2") (pintype "passive"))
      (node (ref "R30") (pin "1") (pinfunction "1_1") (pintype "passive"))
      (node (ref "R32") (pin "2") (pinfunction "2_2") (pintype "passive"))
      (node (ref "R33") (pin "2") (pinfunction "2_2") (pintype "passive"))
      (node (ref "R6") (pin "1") (pinfunction "1_1") (pintype "passive"))
      (node (ref "U1") (pin "18") (pinfunction "VDDIO33_1_18") (pintype "power_in"))
      (node (ref "U1") (pin "92") (pinfunction "VDDIO33_3_92") (pintype "power_in"))
    )
    (net (code "85") (name "GND") (class "Default")
      (node (ref "C1") (pin "1") (pinfunction "1_1") (pintype "passive"))
      (node (ref "C10") (pin "1") (pinfunction "1_1") (pintype "passive"))
      (node (ref "C12") (pin "2") (pinfunction "2_2") (pintype "passive"))
      (node (ref "C13") (pin "1") (pinfunction "1_1") (pintype "passive"))
      (node (ref "C14") (pin "1") (pinfunction "1_1") (pintype "passive"))
      (node (ref "C15") (pin "1") (pinfunction "1_1") (pintype "passive"))
      (node (ref "C16") (pin "1") (pinfunction "1_1") (pintype "passive"))
      (node (ref "C17") (pin "1") (pinfunction "1_1") (pintype "passive"))
      (node (ref "C18") (pin "1") (pinfunction "1_1") (pintype "passive"))
      (node (ref "C19") (pin "1") (pinfunction "1_1") (pintype "passive"))
      (node (ref "C20") (pin "2") (pinfunction "2_2") (pintype "passive"))
      (node (ref "C21") (pin "2") (pinfunction "2_2") (pintype "passive"))
      (node (ref "C22") (pin "2") (pinfunction "2_2") (pintype "passive"))
      (node (ref "C24") (pin "2") (pinfunction "2_2") (pintype "passive"))
      (node (ref "C25") (pin "1") (pinfunction "1_1") (pintype "passive"))
      (node (ref "C26") (pin "1") (pinfunction "1_1") (pintype "passive"))
      (node (ref "C27") (pin "1") (pinfunction "1_1") (pintype "passive"))
      (node (ref "C28") (pin "1") (pinfunction "1_1") (pintype "passive"))
      (node (ref "C29") (pin "1") (pinfunction "1_1") (pintype "passive"))
      (node (ref "C3") (pin "1") (pinfunction "1_1") (pintype "passive"))
      (node (ref "C30") (pin "2") (pinfunction "2_2") (pintype "passive"))
      (node (ref "C31") (pin "1") (pinfunction "1_1") (pintype "passive"))
      (node (ref "C32") (pin "1") (pinfunction "1_1") (pintype "passive"))
      (node (ref "C33") (pin "1") (pinfunction "1_1") (pintype "passive"))
      (node (ref "C34") (pin "2") (pinfunction "2_2") (pintype "passive"))
      (node (ref "C35") (pin "1") (pinfunction "1_1") (pintype "passive"))
      (node (ref "C36") (pin "1") (pinfunction "1_1") (pintype "passive"))
      (node (ref "C37") (pin "1") (pinfunction "1_1") (pintype "passive"))
      (node (ref "C39") (pin "2") (pinfunction "2_2") (pintype "passive"))
      (node (ref "C4") (pin "1") (pinfunction "1_1") (pintype "passive"))
      (node (ref "C41") (pin "2") (pinfunction "2_2") (pintype "passive"))
      (node (ref "C42") (pin "2") (pinfunction "2_2") (pintype "passive"))
      (node (ref "C5") (pin "1") (pinfunction "1_1") (pintype "passive"))
      (node (ref "C6") (pin "2") (pinfunction "2_2") (pintype "passive"))
      (node (ref "C7") (pin "1") (pinfunction "1_1") (pintype "passive"))
      (node (ref "C8") (pin "1") (pinfunction "1_1") (pintype "passive"))
      (node (ref "C9") (pin "1") (pinfunction "1_1") (pintype "passive"))
      (node (ref "J1") (pin "GND") (pinfunction "GND_GND") (pintype "bidirectional"))
      (node (ref "J1") (pin "GND@1") (pinfunction "GND_GND@1") (pintype "bidirectional"))
      (node (ref "J1") (pin "GND@2") (pinfunction "GND_GND@2") (pintype "bidirectional"))
      (node (ref "J4") (pin "11") (pinfunction "GND_11") (pintype "bidirectional"))
      (node (ref "J4") (pin "12") (pinfunction "GND_12") (pintype "bidirectional"))
      (node (ref "J4") (pin "6") (pinfunction "VSS_6") (pintype "bidirectional"))
      (node (ref "J5") (pin "3") (pinfunction "3_3") (pintype "passive"))
      (node (ref "L3") (pin "2") (pinfunction "P$2_2") (pintype "bidirectional"))
      (node (ref "R1") (pin "1") (pinfunction "1_1") (pintype "passive"))
      (node (ref "R10") (pin "1") (pinfunction "1_1") (pintype "passive"))
      (node (ref "R12") (pin "1") (pinfunction "1_1") (pintype "passive"))
      (node (ref "R19") (pin "2") (pinfunction "2_2") (pintype "passive"))
      (node (ref "R20") (pin "1") (pinfunction "1_1") (pintype "passive"))
      (node (ref "R22") (pin "2") (pinfunction "2_2") (pintype "passive"))
      (node (ref "R24") (pin "2") (pinfunction "2_2") (pintype "passive"))
      (node (ref "R34") (pin "1") (pinfunction "1_1") (pintype "passive"))
      (node (ref "R35") (pin "1") (pinfunction "1_1") (pintype "passive"))
      (node (ref "R7") (pin "1") (pinfunction "1_1") (pintype "passive"))
      (node (ref "S1") (pin "P$1") (pinfunction "1_P$1") (pintype "passive"))
      (node (ref "TVS1") (pin "1") (pinfunction "A_1") (pintype "passive"))
      (node (ref "U1") (pin "100") (pinfunction "DCDC_BATTERY_100") (pintype "power_in"))
      (node (ref "U1") (pin "103") (pinfunction "BATT_103") (pintype "input"))
      (node (ref "U1") (pin "105") (pinfunction "VSSA4_105") (pintype "power_in"))
      (node (ref "U1") (pin "112") (pinfunction "VSSA1_112") (pintype "power_in"))
      (node (ref "U1") (pin "118") (pinfunction "VSSA2_118") (pintype "power_in"))
      (node (ref "U1") (pin "119") (pinfunction "PSWITCH_119") (pintype "input"))
      (node (ref "U1") (pin "30") (pinfunction "VSSD1_30") (pintype "power_in"))
      (node (ref "U1") (pin "35") (pinfunction "VSSD2_35") (pintype "power_in"))
      (node (ref "U1") (pin "98") (pinfunction "DCDC_GND_98") (pintype "power_in"))
      (node (ref "U2") (pin "2") (pinfunction "GND_2") (pintype "power_in"))
      (node (ref "U3") (pin "2") (pinfunction "V-_2") (pintype "power_in"))
      (node (ref "U4") (pin "12") (pinfunction "VSSQ2_12") (pintype "power_in"))
      (node (ref "U4") (pin "34") (pinfunction "VSS1_34") (pintype "power_in"))
      (node (ref "U4") (pin "48") (pinfunction "VSS2_48") (pintype "power_in"))
      (node (ref "U4") (pin "52") (pinfunction "VSSQ3_52") (pintype "power_in"))
      (node (ref "U4") (pin "58") (pinfunction "VSSQ4_58") (pintype "power_in"))
      (node (ref "U4") (pin "6") (pinfunction "VSSQ1_6") (pintype "power_in"))
      (node (ref "U4") (pin "64") (pinfunction "VSSQ5_64") (pintype "power_in"))
      (node (ref "U4") (pin "66") (pinfunction "VSS3_66") (pintype "power_in"))
      (node (ref "U5") (pin "2") (pinfunction "V-_2") (pintype "power_in"))
    )
    (net (code "86") (name "LB+5V") (class "Default")
      (node (ref "C2") (pin "1") (pinfunction "1_1") (pintype "passive"))
      (node (ref "C23") (pin "2") (pinfunction "2_2") (pintype "passive"))
      (node (ref "J2") (pin "VCC1") (pinfunction "VCC_VCC1") (pintype "bidirectional"))
      (node (ref "J3") (pin "VCC") (pinfunction "VCC_VCC") (pintype "bidirectional"))
      (node (ref "L2") (pin "1") (pinfunction "P$1_1") (pintype "bidirectional"))
    )
    (net (code "87") (name "LBGND") (class "Default")
      (node (ref "C11") (pin "2") (pinfunction "2_2") (pintype "passive"))
      (node (ref "C40") (pin "2") (pinfunction "2_2") (pintype "passive"))
      (node (ref "C43") (pin "2") (pinfunction "2_2") (pintype "passive"))
      (node (ref "J2") (pin "GND1") (pinfunction "GND_GND1") (pintype "bidirectional"))
      (node (ref "J3") (pin "GND") (pinfunction "GND_GND") (pintype "bidirectional"))
      (node (ref "L3") (pin "1") (pinfunction "P$1_1") (pintype "bidirectional"))
    )
    (net (code "88") (name "Net-(C2-Pad2)") (class "Default")
      (node (ref "C2") (pin "2") (pinfunction "2_2") (pintype "passive"))
      (node (ref "R1") (pin "2") (pinfunction "2_2") (pintype "passive"))
      (node (ref "R2") (pin "2") (pinfunction "2_2") (pintype "passive"))
    )
    (net (code "89") (name "Net-(C23-Pad1)") (class "Default")
      (node (ref "C23") (pin "1") (pinfunction "1_1") (pintype "passive"))
      (node (ref "R8") (pin "1") (pinfunction "1_1") (pintype "passive"))
    )
    (net (code "90") (name "Net-(D1-K)") (class "Default")
      (node (ref "D1") (pin "3") (pinfunction "K_3") (pintype "passive"))
      (node (ref "J5") (pin "1") (pinfunction "1_1") (pintype "passive"))
    )
    (net (code "91") (name "Net-(J2-SIG)") (class "Default")
      (node (ref "C11") (pin "1") (pinfunction "1_1") (pintype "passive"))
      (node (ref "C40") (pin "1") (pinfunction "1_1") (pintype "passive"))
      (node (ref "C41") (pin "1") (pinfunction "1_1") (pintype "passive"))
      (node (ref "C42") (pin "1") (pinfunction "1_1") (pintype "passive"))
      (node (ref "J2") (pin "SIG1") (pinfunction "SIG_SIG1") (pintype "bidirectional"))
      (node (ref "R12") (pin "2") (pinfunction "2_2") (pintype "passive"))
      (node (ref "R13") (pin "1") (pinfunction "1_1") (pintype "passive"))
    )
    (net (code "92") (name "Net-(LED1-BLU)") (class "Default")
      (node (ref "LED1") (pin "3") (pinfunction "BLU_3") (pintype "bidirectional"))
      (node (ref "R29") (pin "2") (pinfunction "2_2") (pintype "passive"))
    )
    (net (code "93") (name "Net-(LED1-GRN)") (class "Default")
      (node (ref "LED1") (pin "4") (pinfunction "GRN_4") (pintype "bidirectional"))
      (node (ref "R28") (pin "2") (pinfunction "2_2") (pintype "passive"))
    )
    (net (code "94") (name "Net-(LED1-RED)") (class "Default")
      (node (ref "LED1") (pin "1") (pinfunction "RED_1") (pintype "bidirectional"))
      (node (ref "R27") (pin "2") (pinfunction "2_2") (pintype "passive"))
    )
    (net (code "95") (name "Net-(S1-2)") (class "Default")
      (node (ref "R11") (pin "1") (pinfunction "1_1") (pintype "passive"))
      (node (ref "R9") (pin "1") (pinfunction "1_1") (pintype "passive"))
      (node (ref "S1") (pin "P$2") (pinfunction "2_P$2") (pintype "passive"))
    )
    (net (code "96") (name "Net-(TVS1-C)") (class "Default")
      (node (ref "R13") (pin "2") (pinfunction "2_2") (pintype "passive"))
      (node (ref "TVS1") (pin "2") (pinfunction "C_2") (pintype "passive"))
      (node (ref "U3") (pin "1") (pinfunction "+IN_1") (pintype "input"))
    )
    (net (code "97") (name "Net-(U1-GPMI_WRN{slash}SSP2_SCK)") (class "Default")
      (node (ref "R8") (pin "2") (pinfunction "2_2") (pintype "passive"))
      (node (ref "U1") (pin "33") (pinfunction "GPMI_WRN/SSP2_SCK_33") (pintype "bidirectional"))
    )
    (net (code "98") (name "Net-(U1-LRADC1)") (class "Default")
      (node (ref "C6") (pin "1") (pinfunction "1_1") (pintype "passive"))
      (node (ref "R2") (pin "1") (pinfunction "1_1") (pintype "passive"))
      (node (ref "U1") (pin "107") (pinfunction "LRADC1_107") (pintype "bidirectional"))
    )
    (net (code "99") (name "Net-(U1-VAG)") (class "Default")
      (node (ref "C14") (pin "2") (pinfunction "2_2") (pintype "passive"))
      (node (ref "U1") (pin "117") (pinfunction "VAG_117") (pintype "passive"))
    )
    (net (code "100") (name "Net-(U1-VDDA1)") (class "Default")
      (node (ref "C13") (pin "2") (pinfunction "2_2") (pintype "passive"))
      (node (ref "U1") (pin "110") (pinfunction "VDDA1_110") (pintype "power_in"))
    )
    (net (code "101") (name "Net-(U2-OUT)") (class "Default")
      (node (ref "L1") (pin "2") (pinfunction "2_2") (pintype "passive"))
      (node (ref "U2") (pin "1") (pinfunction "OUT_1") (pintype "bidirectional"))
    )
    (net (code "102") (name "Net-(U3--IN)") (class "Default")
      (node (ref "R18") (pin "2") (pinfunction "2_2") (pintype "passive"))
      (node (ref "U3") (pin "3") (pinfunction "-IN_3") (pintype "input"))
      (node (ref "U3") (pin "4") (pinfunction "OUT_4") (pintype "output"))
    )
    (net (code "103") (name "Net-(U4-VREF)") (class "Default")
      (node (ref "C35") (pin "2") (pinfunction "2_2") (pintype "passive"))
      (node (ref "C38") (pin "2") (pinfunction "2_2") (pintype "passive"))
      (node (ref "R20") (pin "2") (pinfunction "2_2") (pintype "passive"))
      (node (ref "R23") (pin "1") (pinfunction "1_1") (pintype "passive"))
      (node (ref "U4") (pin "49") (pinfunction "VREF_49") (pintype "input"))
    )
    (net (code "104") (name "Net-(U5--IN)") (class "Default")
      (node (ref "R24") (pin "1") (pinfunction "1_1") (pintype "passive"))
      (node (ref "R26") (pin "2") (pinfunction "2_2") (pintype "passive"))
      (node (ref "U5") (pin "3") (pinfunction "-IN_3") (pintype "input"))
    )
    (net (code "105") (name "Net-(U5-OUT)") (class "Default")
      (node (ref "C43") (pin "1") (pinfunction "1_1") (pintype "passive"))
      (node (ref "J3") (pin "SIG") (pinfunction "SIG_SIG") (pintype "bidirectional"))
      (node (ref "R26") (pin "1") (pinfunction "1_1") (pintype "passive"))
      (node (ref "U5") (pin "4") (pinfunction "OUT_4") (pintype "output"))
    )
    (net (code "106") (name "unconnected-(D1-A1-Pad1)") (class "Default")
      (node (ref "D1") (pin "1") (pinfunction "A1_1") (pintype "passive"))
    )
    (net (code "107") (name "unconnected-(J4-DET-Pad9)") (class "Default")
      (node (ref "J4") (pin "9") (pinfunction "DET_9") (pintype "bidirectional"))
    )
    (net (code "108") (name "unconnected-(J4-DET-Pad10)") (class "Default")
      (node (ref "J4") (pin "10") (pinfunction "DET_10") (pintype "bidirectional"))
    )
    (net (code "109") (name "unconnected-(U1-DCDC_LN1-Pad97)") (class "Default")
      (node (ref "U1") (pin "97") (pinfunction "DCDC_LN1_97") (pintype "passive"))
    )
    (net (code "110") (name "unconnected-(U1-DCDC_LP-Pad99)") (class "Default")
      (node (ref "U1") (pin "99") (pinfunction "DCDC_LP_99") (pintype "passive"))
    )
    (net (code "111") (name "unconnected-(U1-GPMI_CE0N-Pad82)") (class "Default")
      (node (ref "U1") (pin "82") (pinfunction "GPMI_CE0N_82") (pintype "bidirectional"))
    )
    (net (code "112") (name "unconnected-(U1-GPMI_CE1N-Pad81)") (class "Default")
      (node (ref "U1") (pin "81") (pinfunction "GPMI_CE1N_81") (pintype "bidirectional"))
    )
    (net (code "113") (name "unconnected-(U1-GPMI_CLE{slash}LCD_D16-Pad19)") (class "Default")
      (node (ref "U1") (pin "19") (pinfunction "GPMI_CLE/LCD_D16_19") (pintype "bidirectional"))
    )
    (net (code "114") (name "unconnected-(U1-GPMI_D00{slash}LCD_D08{slash}SSP2_DATA0-Pad22)") (class "Default")
      (node (ref "U1") (pin "22") (pinfunction "GPMI_D00/LCD_D08/SSP2_DATA0_22") (pintype "bidirectional"))
    )
    (net (code "115") (name "unconnected-(U1-GPMI_D01{slash}LCD_D09{slash}SSP2_DATA1-Pad23)") (class "Default")
      (node (ref "U1") (pin "23") (pinfunction "GPMI_D01/LCD_D09/SSP2_DATA1_23") (pintype "bidirectional"))
    )
    (net (code "116") (name "unconnected-(U1-GPMI_D02{slash}LCD_D10{slash}SSP2_DATA2-Pad24)") (class "Default")
      (node (ref "U1") (pin "24") (pinfunction "GPMI_D02/LCD_D10/SSP2_DATA2_24") (pintype "bidirectional"))
    )
    (net (code "117") (name "unconnected-(U1-GPMI_D03{slash}LCD_D11{slash}SSP2_DATA3-Pad25)") (class "Default")
      (node (ref "U1") (pin "25") (pinfunction "GPMI_D03/LCD_D11/SSP2_DATA3_25") (pintype "bidirectional"))
    )
    (net (code "118") (name "unconnected-(U1-GPMI_D04{slash}LCD_D12{slash}SSP2_DATA4-Pad27)") (class "Default")
      (node (ref "U1") (pin "27") (pinfunction "GPMI_D04/LCD_D12/SSP2_DATA4_27") (pintype "bidirectional"))
    )
    (net (code "119") (name "unconnected-(U1-GPMI_D05{slash}LCD_D13{slash}SSP2_DATA5-Pad26)") (class "Default")
      (node (ref "U1") (pin "26") (pinfunction "GPMI_D05/LCD_D13/SSP2_DATA5_26") (pintype "bidirectional"))
    )
    (net (code "120") (name "unconnected-(U1-GPMI_D06{slash}LCD_D14{slash}SSP2_DATA6-Pad29)") (class "Default")
      (node (ref "U1") (pin "29") (pinfunction "GPMI_D06/LCD_D14/SSP2_DATA6_29") (pintype "bidirectional"))
    )
    (net (code "121") (name "unconnected-(U1-GPMI_D07{slash}LCD_D15{slash}SSP2_DATA7-Pad28)") (class "Default")
      (node (ref "U1") (pin "28") (pinfunction "GPMI_D07/LCD_D15/SSP2_DATA7_28") (pintype "bidirectional"))
    )
    (net (code "122") (name "unconnected-(U1-GPMI_RDN-Pad31)") (class "Default")
      (node (ref "U1") (pin "31") (pinfunction "GPMI_RDN_31") (pintype "bidirectional"))
    )
    (net (code "123") (name "unconnected-(U1-GPMI_RDY0{slash}SSP2_DETECT-Pad32)") (class "Default")
      (node (ref "U1") (pin "32") (pinfunction "GPMI_RDY0/SSP2_DETECT_32") (pintype "bidirectional"))
    )
    (net (code "124") (name "unconnected-(U1-GPMI_RDY1{slash}SSP2_CMD-Pad21)") (class "Default")
      (node (ref "U1") (pin "21") (pinfunction "GPMI_RDY1/SSP2_CMD_21") (pintype "bidirectional"))
    )
    (net (code "125") (name "unconnected-(U1-LCD_CS-Pad10)") (class "Default")
      (node (ref "U1") (pin "10") (pinfunction "LCD_CS_10") (pintype "bidirectional"))
    )
    (net (code "126") (name "unconnected-(U1-LCD_D04-Pad6)") (class "Default")
      (node (ref "U1") (pin "6") (pinfunction "LCD_D04_6") (pintype "bidirectional"))
    )
    (net (code "127") (name "unconnected-(U1-LCD_D05-Pad7)") (class "Default")
      (node (ref "U1") (pin "7") (pinfunction "LCD_D05_7") (pintype "bidirectional"))
    )
    (net (code "128") (name "unconnected-(U1-LCD_D06-Pad8)") (class "Default")
      (node (ref "U1") (pin "8") (pinfunction "LCD_D06_8") (pintype "bidirectional"))
    )
    (net (code "129") (name "unconnected-(U1-LCD_DOTCK{slash}GPMI_RDY3-Pad17)") (class "Default")
      (node (ref "U1") (pin "17") (pinfunction "LCD_DOTCK/GPMI_RDY3_17") (pintype "bidirectional"))
    )
    (net (code "130") (name "unconnected-(U1-LCD_ENABLE{slash}I2C_SCL-Pad11)") (class "Default")
      (node (ref "U1") (pin "11") (pinfunction "LCD_ENABLE/I2C_SCL_11") (pintype "bidirectional"))
    )
    (net (code "131") (name "unconnected-(U1-LCD_HSYNC{slash}I2C_SDA-Pad15)") (class "Default")
      (node (ref "U1") (pin "15") (pinfunction "LCD_HSYNC/I2C_SDA_15") (pintype "bidirectional"))
    )
    (net (code "132") (name "unconnected-(U1-LCD_RESET{slash}GPMI_CE3N-Pad12)") (class "Default")
      (node (ref "U1") (pin "12") (pinfunction "LCD_RESET/GPMI_CE3N_12") (pintype "bidirectional"))
    )
    (net (code "133") (name "unconnected-(U1-LCD_VSYNC{slash}LCD_BUSY-Pad16)") (class "Default")
      (node (ref "U1") (pin "16") (pinfunction "LCD_VSYNC/LCD_BUSY_16") (pintype "bidirectional"))
    )
    (net (code "134") (name "unconnected-(U1-LCD_WR-Pad13)") (class "Default")
      (node (ref "U1") (pin "13") (pinfunction "LCD_WR_13") (pintype "bidirectional"))
    )
    (net (code "135") (name "unconnected-(U1-LINE1_INR-Pad114)") (class "Default")
      (node (ref "U1") (pin "114") (pinfunction "LINE1_INR_114") (pintype "input"))
    )
    (net (code "136") (name "unconnected-(U1-MIC-Pad116)") (class "Default")
      (node (ref "U1") (pin "116") (pinfunction "MIC_116") (pintype "input"))
    )
    (net (code "137") (name "unconnected-(U1-SSP1_DETECT{slash}GPMI_CE3N{slash}USB_ID-Pad88)") (class "Default")
      (node (ref "U1") (pin "88") (pinfunction "SSP1_DETECT/GPMI_CE3N/USB_ID_88") (pintype "bidirectional"))
    )
    (net (code "138") (name "unconnected-(U4-NC1-Pad14)") (class "Default")
      (node (ref "U4") (pin "14") (pinfunction "NC1_14") (pintype "no_connect"))
    )
    (net (code "139") (name "unconnected-(U4-NC2-Pad17)") (class "Default")
      (node (ref "U4") (pin "17") (pinfunction "NC2_17") (pintype "no_connect"))
    )
    (net (code "140") (name "unconnected-(U4-NC3-Pad19)") (class "Default")
      (node (ref "U4") (pin "19") (pinfunction "NC3_19") (pintype "no_connect"))
    )
    (net (code "141") (name "unconnected-(U4-NC4-Pad25)") (class "Default")
      (node (ref "U4") (pin "25") (pinfunction "NC4_25") (pintype "no_connect"))
    )
    (net (code "142") (name "unconnected-(U4-NC5-Pad43)") (class "Default")
      (node (ref "U4") (pin "43") (pinfunction "NC5_43") (pintype "no_connect"))
    )
    (net (code "143") (name "unconnected-(U4-NC6-Pad50)") (class "Default")
      (node (ref "U4") (pin "50") (pinfunction "NC6_50") (pintype "no_connect"))
    )
    (net (code "144") (name "unconnected-(U4-NC7-Pad53)") (class "Default")
      (node (ref "U4") (pin "53") (pinfunction "NC7_53") (pintype "no_connect"))
    )
  )
)
